# KGGRS2.net
KiCad netlist of a schematic drawn in EAGLE
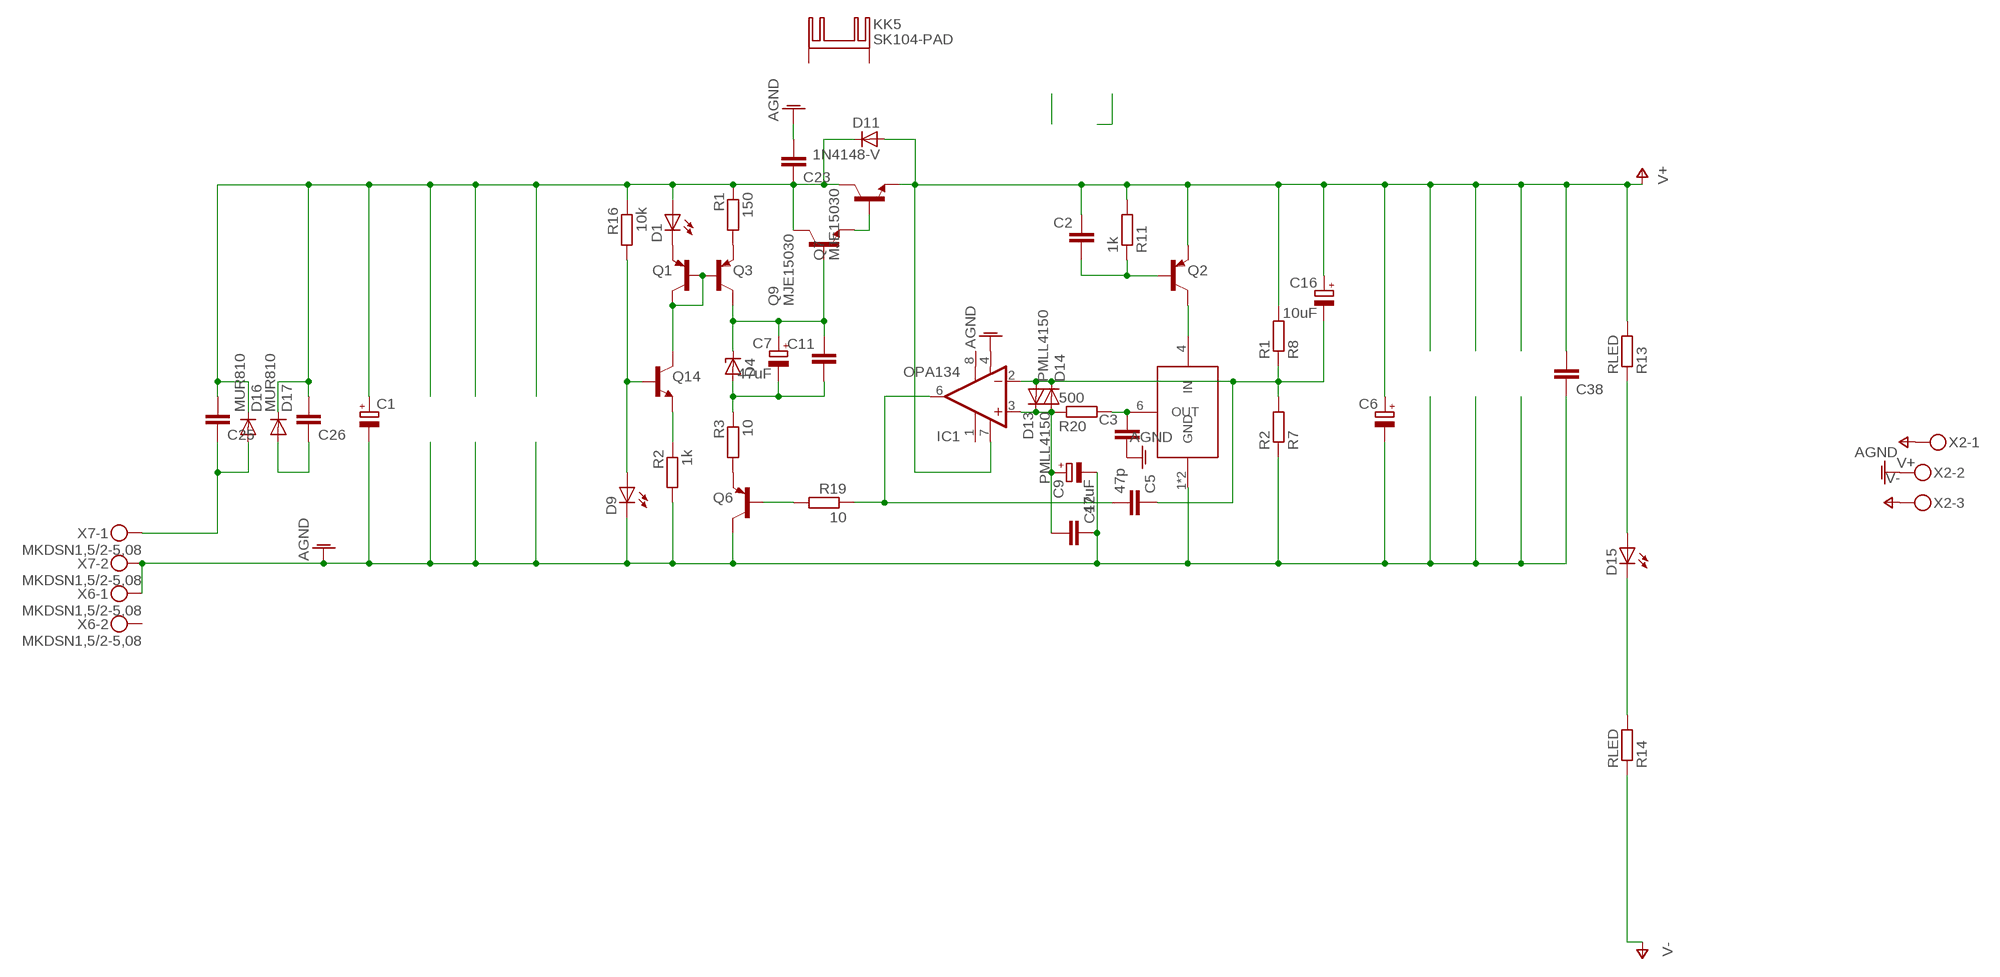
[diagram p0: schematic, sheet 1]

(export (version "E")
  (design (tool "Eeschema 10.0.6"))
  (components
    (comp (ref "C1")
      (value "CPOL-EUE10-35")
      (footprint "eagle-import:EB35D")
      (libsource (lib "eagle-import") (part "CPOL-EUE10-35"))
    )
    (comp (ref "C2")
      (value "C-EUC1206")
      (footprint "eagle-import:C1206")
      (libsource (lib "eagle-import") (part "C-EUC1206"))
    )
    (comp (ref "C3")
      (value "C-EUC1206")
      (footprint "eagle-import:C1206")
      (libsource (lib "eagle-import") (part "C-EUC1206"))
    )
    (comp (ref "C5")
      (value "47p")
      (footprint "eagle-import:C1206")
      (libsource (lib "eagle-import") (part "C-EUC1206"))
    )
    (comp (ref "C6")
      (value "CPOL-EUE5-13")
      (footprint "eagle-import:E5-13")
      (libsource (lib "eagle-import") (part "CPOL-EUE5-13"))
    )
    (comp (ref "C7")
      (value "47uF")
      (footprint "eagle-import:SP-CAP-CX")
      (libsource (lib "eagle-import") (part "CPOL-EUSP-CAP-CX"))
    )
    (comp (ref "C9")
      (value "47uF")
      (footprint "eagle-import:SP-CAP-CX")
      (libsource (lib "eagle-import") (part "CPOL-EUSP-CAP-CX"))
    )
    (comp (ref "C11")
      (value "C-EUC1206")
      (footprint "eagle-import:C1206")
      (libsource (lib "eagle-import") (part "C-EUC1206"))
    )
    (comp (ref "C12")
      (value "C-EU050-035X075")
      (footprint "eagle-import:C050-035X075")
      (libsource (lib "eagle-import") (part "C-EU050-035X075"))
    )
    (comp (ref "C16")
      (value "10uF")
      (footprint "eagle-import:SP-CAP-CX")
      (libsource (lib "eagle-import") (part "CPOL-EUSP-CAP-CX"))
    )
    (comp (ref "C23")
      (value "C-EU050-075X075")
      (footprint "eagle-import:C050-075X075")
      (libsource (lib "eagle-import") (part "C-EU050-075X075"))
    )
    (comp (ref "C25")
      (value "C-EU050-035X075")
      (footprint "eagle-import:C050-035X075")
      (libsource (lib "eagle-import") (part "C-EU050-035X075"))
    )
    (comp (ref "C26")
      (value "C-EU050-035X075")
      (footprint "eagle-import:C050-035X075")
      (libsource (lib "eagle-import") (part "C-EU050-035X075"))
    )
    (comp (ref "C38")
      (value "C-EU050-035X075")
      (footprint "eagle-import:C050-035X075")
      (libsource (lib "eagle-import") (part "C-EU050-035X075"))
    )
    (comp (ref "D1")
      (value "LED5MM")
      (footprint "eagle-import:LED5MM")
      (libsource (lib "eagle-import") (part "LED5MM"))
    )
    (comp (ref "D4")
      (value "ZENER-DIODESOD80C")
      (footprint "eagle-import:SOD80C")
      (libsource (lib "eagle-import") (part "ZENER-DIODESOD80C"))
    )
    (comp (ref "D9")
      (value "LED5MM")
      (footprint "eagle-import:LED5MM")
      (libsource (lib "eagle-import") (part "LED5MM"))
    )
    (comp (ref "D11")
      (value "1N4148-V")
      (footprint "eagle-import:1N4148")
      (libsource (lib "eagle-import") (part "1N4148-V"))
    )
    (comp (ref "D13")
      (value "PMLL4150")
      (footprint "eagle-import:SOD80C")
      (libsource (lib "eagle-import") (part "PMLL4150"))
    )
    (comp (ref "D14")
      (value "PMLL4150")
      (footprint "eagle-import:SOD80C")
      (libsource (lib "eagle-import") (part "PMLL4150"))
    )
    (comp (ref "D15")
      (value "LED5MM")
      (footprint "eagle-import:LED5MM")
      (libsource (lib "eagle-import") (part "LED5MM"))
    )
    (comp (ref "D16")
      (value "MUR810")
      (footprint "eagle-import:TO220ACS")
      (libsource (lib "eagle-import") (part "MUR810"))
    )
    (comp (ref "D17")
      (value "MUR810")
      (footprint "eagle-import:TO220ACS")
      (libsource (lib "eagle-import") (part "MUR810"))
    )
    (comp (ref "IC1")
      (value "OPA134")
      (footprint "eagle-import:SO08")
      (fields (field (name "MF") "TEXAS INSTRUMENTS") (field (name "MPN") "OPA134UA"))
      (libsource (lib "eagle-import") (part "OPA134U"))
    )
    (comp (ref "KK5")
      (value "SK104-PAD")
      (footprint "eagle-import:SK104-PAD")
      (libsource (lib "eagle-import") (part "SK104-PAD"))
    )
    (comp (ref "Q1")
      (value "MMBTA92LT1-PNP-SOT23-BEC")
      (footprint "eagle-import:SOT23-BEC")
      (libsource (lib "eagle-import") (part "-PNP-SOT23-BECMMBTA92LT1"))
    )
    (comp (ref "Q2")
      (value "MMBTA92LT1-PNP-SOT23-BEC")
      (footprint "eagle-import:SOT23-BEC")
      (libsource (lib "eagle-import") (part "-PNP-SOT23-BECMMBTA92LT1"))
    )
    (comp (ref "Q3")
      (value "MMBTA92LT1-PNP-SOT23-BEC")
      (footprint "eagle-import:SOT23-BEC")
      (libsource (lib "eagle-import") (part "-PNP-SOT23-BECMMBTA92LT1"))
    )
    (comp (ref "Q6")
      (value "MMBTA92LT1-PNP-SOT23-BEC")
      (footprint "eagle-import:SOT23-BEC")
      (libsource (lib "eagle-import") (part "-PNP-SOT23-BECMMBTA92LT1"))
    )
    (comp (ref "Q7")
      (value "MJE15030")
      (footprint "eagle-import:TO220KG")
      (libsource (lib "eagle-import") (part "MJE15030"))
    )
    (comp (ref "Q9")
      (value "MJE15030")
      (footprint "eagle-import:TO220KG")
      (libsource (lib "eagle-import") (part "MJE15030"))
    )
    (comp (ref "Q14")
      (value "MMBTA42LT1-NPN-SOT23-BEC")
      (footprint "eagle-import:SOT23-BEC")
      (libsource (lib "eagle-import") (part "-NPN-SOT23-BECMMBTA42LT1"))
    )
    (comp (ref "R1")
      (value "150")
      (footprint "eagle-import:MINI_MELF-0204W")
      (libsource (lib "eagle-import") (part "R-EU_MELF0204W"))
    )
    (comp (ref "R2")
      (value "1k")
      (footprint "eagle-import:MINI_MELF-0204W")
      (libsource (lib "eagle-import") (part "R-EU_MELF0204W"))
    )
    (comp (ref "R3")
      (value "10")
      (footprint "eagle-import:MINI_MELF-0204W")
      (libsource (lib "eagle-import") (part "R-EU_MELF0204W"))
    )
    (comp (ref "R7")
      (value "R2")
      (footprint "eagle-import:MINI_MELF-0204W")
      (libsource (lib "eagle-import") (part "R-EU_MELF0204W"))
    )
    (comp (ref "R8")
      (value "R1")
      (footprint "eagle-import:MINI_MELF-0204W")
      (libsource (lib "eagle-import") (part "R-EU_MELF0204W"))
    )
    (comp (ref "R11")
      (value "1k")
      (footprint "eagle-import:MINI_MELF-0204W")
      (libsource (lib "eagle-import") (part "R-EU_MELF0204W"))
    )
    (comp (ref "R13")
      (value "RLED")
      (footprint "eagle-import:MINI_MELF-0204W")
      (libsource (lib "eagle-import") (part "R-EU_MELF0204W"))
    )
    (comp (ref "R14")
      (value "RLED")
      (footprint "eagle-import:0207_2V")
      (libsource (lib "eagle-import") (part "R-EU_0207/2V"))
    )
    (comp (ref "R16")
      (value "10k")
      (footprint "eagle-import:MINI_MELF-0204W")
      (libsource (lib "eagle-import") (part "R-EU_MELF0204W"))
    )
    (comp (ref "R19")
      (value "10")
      (footprint "eagle-import:MINI_MELF-0204W")
      (libsource (lib "eagle-import") (part "R-EU_MELF0204W"))
    )
    (comp (ref "R20")
      (value "500")
      (footprint "eagle-import:MINI_MELF-0204W")
      (libsource (lib "eagle-import") (part "R-EU_MELF0204W"))
    )
    (comp (ref "U$1")
      (value "LTC6654")
      (footprint "eagle-import:SOT-23-6")
      (libsource (lib "eagle-import") (part "LTC6654"))
    )
    (comp (ref "X2")
      (value "MKDSN1,5/3-5,08")
      (footprint "eagle-import:MKDSN1,5_3-5,08")
      (libsource (lib "eagle-import") (part "MKDSN1,5/3-5,08"))
    )
    (comp (ref "X6")
      (value "MKDSN1,5/2-5,08")
      (footprint "eagle-import:MKDSN1,5_2-5,08")
      (libsource (lib "eagle-import") (part "MKDSN1,5/2-5,08"))
    )
    (comp (ref "X7")
      (value "MKDSN1,5/2-5,08")
      (footprint "eagle-import:MKDSN1,5_2-5,08")
      (libsource (lib "eagle-import") (part "MKDSN1,5/2-5,08"))
    )
  )
  (nets
    (net (code "1") (name "AGND") (class "Default")
      (node (ref "C1") (pin "-") (pinfunction "-_-") (pintype "passive"))
      (node (ref "C12") (pin "1") (pinfunction "1_1") (pintype "passive"))
      (node (ref "C23") (pin "2") (pinfunction "2_2") (pintype "passive"))
      (node (ref "C3") (pin "2") (pinfunction "2_2") (pintype "passive"))
      (node (ref "C38") (pin "1") (pinfunction "1_1") (pintype "passive"))
      (node (ref "C6") (pin "-") (pinfunction "-_-") (pintype "passive"))
      (node (ref "C9") (pin "-") (pinfunction "-_-") (pintype "passive"))
      (node (ref "D9") (pin "K") (pinfunction "C_K") (pintype "passive"))
      (node (ref "IC1") (pin "4") (pinfunction "V-_4") (pintype "power_in"))
      (node (ref "Q6") (pin "C") (pinfunction "C_C") (pintype "passive"))
      (node (ref "R2") (pin "2") (pinfunction "2_2") (pintype "passive"))
      (node (ref "R7") (pin "1") (pinfunction "1_1") (pintype "passive"))
      (node (ref "U$1") (pin "1") (pinfunction "GND_1") (pintype "bidirectional"))
      (node (ref "U$1") (pin "2") (pinfunction "GND_2") (pintype "bidirectional"))
      (node (ref "X2") (pin "2") (pinfunction "KL_2") (pintype "passive"))
      (node (ref "X6") (pin "1") (pinfunction "KL_1") (pintype "passive"))
      (node (ref "X7") (pin "2") (pinfunction "KL_2") (pintype "passive"))
    )
    (net (code "2") (name "Net-(C2-Pad2)") (class "Default")
      (node (ref "C2") (pin "2") (pinfunction "2_2") (pintype "passive"))
      (node (ref "Q2") (pin "B") (pinfunction "B_B") (pintype "passive"))
      (node (ref "R11") (pin "1") (pinfunction "1_1") (pintype "passive"))
    )
    (net (code "3") (name "Net-(C11-Pad2)") (class "Default")
      (node (ref "C11") (pin "2") (pinfunction "2_2") (pintype "passive"))
      (node (ref "C7") (pin "-") (pinfunction "-_-") (pintype "passive"))
      (node (ref "D4") (pin "A") (pinfunction "A_A") (pintype "passive"))
      (node (ref "R3") (pin "1") (pinfunction "1_1") (pintype "passive"))
    )
    (net (code "4") (name "Net-(C26-Pad1)") (class "Default")
      (node (ref "C26") (pin "1") (pinfunction "1_1") (pintype "passive"))
      (node (ref "D17") (pin "A") (pinfunction "A_A") (pintype "passive"))
    )
    (net (code "5") (name "Net-(D1-C)") (class "Default")
      (node (ref "D1") (pin "K") (pinfunction "C_K") (pintype "passive"))
      (node (ref "Q1") (pin "E") (pinfunction "E_E") (pintype "passive"))
    )
    (net (code "6") (name "Net-(D9-PadA)") (class "Default")
      (node (ref "D9") (pin "A") (pinfunction "A_A") (pintype "passive"))
      (node (ref "Q14") (pin "B") (pinfunction "B_B") (pintype "passive"))
      (node (ref "R16") (pin "2") (pinfunction "2_2") (pintype "passive"))
    )
    (net (code "7") (name "Net-(D15-C)") (class "Default")
      (node (ref "D15") (pin "K") (pinfunction "C_K") (pintype "passive"))
      (node (ref "R14") (pin "2") (pinfunction "2_2") (pintype "passive"))
    )
    (net (code "8") (name "Net-(D15-PadA)") (class "Default")
      (node (ref "D15") (pin "A") (pinfunction "A_A") (pintype "passive"))
      (node (ref "R13") (pin "1") (pinfunction "1_1") (pintype "passive"))
    )
    (net (code "9") (name "Net-(IC1-+IN)") (class "Default")
      (node (ref "C12") (pin "2") (pinfunction "2_2") (pintype "passive"))
      (node (ref "C9") (pin "+") (pinfunction "+_+") (pintype "passive"))
      (node (ref "D13") (pin "C") (pinfunction "C_C") (pintype "passive"))
      (node (ref "D14") (pin "A") (pinfunction "A_A") (pintype "passive"))
      (node (ref "IC1") (pin "3") (pinfunction "+IN_3") (pintype "input"))
      (node (ref "R20") (pin "1") (pinfunction "1_1") (pintype "passive"))
    )
    (net (code "10") (name "Net-(IC1--IN)") (class "Default")
      (node (ref "C16") (pin "-") (pinfunction "-_-") (pintype "passive"))
      (node (ref "C5") (pin "1") (pinfunction "1_1") (pintype "passive"))
      (node (ref "D13") (pin "A") (pinfunction "A_A") (pintype "passive"))
      (node (ref "D14") (pin "C") (pinfunction "C_C") (pintype "passive"))
      (node (ref "IC1") (pin "2") (pinfunction "-IN_2") (pintype "input"))
      (node (ref "R7") (pin "2") (pinfunction "2_2") (pintype "passive"))
      (node (ref "R8") (pin "1") (pinfunction "1_1") (pintype "passive"))
    )
    (net (code "11") (name "Net-(IC1-OUT)") (class "Default")
      (node (ref "C5") (pin "2") (pinfunction "2_2") (pintype "passive"))
      (node (ref "IC1") (pin "6") (pinfunction "OUT_6") (pintype "output"))
      (node (ref "R19") (pin "1") (pinfunction "1_1") (pintype "passive"))
    )
    (net (code "12") (name "Net-(Q1-PadB)") (class "Default")
      (node (ref "Q1") (pin "B") (pinfunction "B_B") (pintype "passive"))
      (node (ref "Q1") (pin "C") (pinfunction "C_C") (pintype "passive"))
      (node (ref "Q14") (pin "C") (pinfunction "C_C") (pintype "passive"))
      (node (ref "Q3") (pin "B") (pinfunction "B_B") (pintype "passive"))
    )
    (net (code "13") (name "Net-(Q3-PadE)") (class "Default")
      (node (ref "Q3") (pin "E") (pinfunction "E_E") (pintype "passive"))
      (node (ref "R1") (pin "2") (pinfunction "2_2") (pintype "passive"))
    )
    (net (code "14") (name "Net-(Q6-PadB)") (class "Default")
      (node (ref "Q6") (pin "B") (pinfunction "B_B") (pintype "passive"))
      (node (ref "R19") (pin "2") (pinfunction "2_2") (pintype "passive"))
    )
    (net (code "15") (name "Net-(Q6-PadE)") (class "Default")
      (node (ref "Q6") (pin "E") (pinfunction "E_E") (pintype "passive"))
      (node (ref "R3") (pin "2") (pinfunction "2_2") (pintype "passive"))
    )
    (net (code "16") (name "Net-(Q7-B)") (class "Default")
      (node (ref "Q7") (pin "1") (pinfunction "B_1") (pintype "passive"))
      (node (ref "Q9") (pin "3") (pinfunction "E_3") (pintype "passive"))
    )
    (net (code "17") (name "Net-(Q7-C)") (class "Default")
      (node (ref "C1") (pin "+") (pinfunction "+_+") (pintype "passive"))
      (node (ref "C23") (pin "1") (pinfunction "1_1") (pintype "passive"))
      (node (ref "C25") (pin "2") (pinfunction "2_2") (pintype "passive"))
      (node (ref "C26") (pin "2") (pinfunction "2_2") (pintype "passive"))
      (node (ref "D1") (pin "A") (pinfunction "A_A") (pintype "passive"))
      (node (ref "D11") (pin "C") (pinfunction "C_C") (pintype "passive"))
      (node (ref "D16") (pin "C") (pinfunction "C_C") (pintype "passive"))
      (node (ref "D17") (pin "C") (pinfunction "C_C") (pintype "passive"))
      (node (ref "Q7") (pin "2") (pinfunction "C_2") (pintype "passive"))
      (node (ref "Q9") (pin "2") (pinfunction "C_2") (pintype "passive"))
      (node (ref "R1") (pin "1") (pinfunction "1_1") (pintype "passive"))
      (node (ref "R16") (pin "1") (pinfunction "1_1") (pintype "passive"))
    )
    (net (code "18") (name "Net-(Q9-B)") (class "Default")
      (node (ref "C11") (pin "1") (pinfunction "1_1") (pintype "passive"))
      (node (ref "C7") (pin "+") (pinfunction "+_+") (pintype "passive"))
      (node (ref "D4") (pin "C") (pinfunction "C_C") (pintype "passive"))
      (node (ref "Q3") (pin "C") (pinfunction "C_C") (pintype "passive"))
      (node (ref "Q9") (pin "1") (pinfunction "B_1") (pintype "passive"))
    )
    (net (code "19") (name "Net-(Q14-PadE)") (class "Default")
      (node (ref "Q14") (pin "E") (pinfunction "E_E") (pintype "passive"))
      (node (ref "R2") (pin "1") (pinfunction "1_1") (pintype "passive"))
    )
    (net (code "20") (name "Net-(U$1-IN)") (class "Default")
      (node (ref "Q2") (pin "C") (pinfunction "C_C") (pintype "passive"))
      (node (ref "U$1") (pin "4") (pinfunction "IN_4") (pintype "bidirectional"))
    )
    (net (code "21") (name "Net-(U$1-OUT)") (class "Default")
      (node (ref "C3") (pin "1") (pinfunction "1_1") (pintype "passive"))
      (node (ref "R20") (pin "2") (pinfunction "2_2") (pintype "passive"))
      (node (ref "U$1") (pin "6") (pinfunction "OUT_6") (pintype "bidirectional"))
    )
    (net (code "22") (name "Net-(X7A-KL)") (class "Default")
      (node (ref "C25") (pin "1") (pinfunction "1_1") (pintype "passive"))
      (node (ref "D16") (pin "A") (pinfunction "A_A") (pintype "passive"))
      (node (ref "X7") (pin "1") (pinfunction "KL_1") (pintype "passive"))
    )
    (net (code "23") (name "V+") (class "Default")
      (node (ref "C16") (pin "+") (pinfunction "+_+") (pintype "passive"))
      (node (ref "C2") (pin "1") (pinfunction "1_1") (pintype "passive"))
      (node (ref "C38") (pin "2") (pinfunction "2_2") (pintype "passive"))
      (node (ref "C6") (pin "+") (pinfunction "+_+") (pintype "passive"))
      (node (ref "D11") (pin "A") (pinfunction "A_A") (pintype "passive"))
      (node (ref "IC1") (pin "7") (pinfunction "V+_7") (pintype "power_in"))
      (node (ref "Q2") (pin "E") (pinfunction "E_E") (pintype "passive"))
      (node (ref "Q7") (pin "3") (pinfunction "E_3") (pintype "passive"))
      (node (ref "R11") (pin "2") (pinfunction "2_2") (pintype "passive"))
      (node (ref "R13") (pin "2") (pinfunction "2_2") (pintype "passive"))
      (node (ref "R8") (pin "2") (pinfunction "2_2") (pintype "passive"))
      (node (ref "X2") (pin "1") (pinfunction "KL_1") (pintype "passive"))
    )
    (net (code "24") (name "V-") (class "Default")
      (node (ref "R14") (pin "1") (pinfunction "1_1") (pintype "passive"))
      (node (ref "X2") (pin "3") (pinfunction "KL_3") (pintype "passive"))
    )
    (net (code "25") (name "unconnected-(IC1-TRIM1-Pad1)") (class "Default")
      (node (ref "IC1") (pin "1") (pinfunction "TRIM1_1") (pintype "passive"))
    )
    (net (code "26") (name "unconnected-(IC1-TRIM2-Pad8)") (class "Default")
      (node (ref "IC1") (pin "8") (pinfunction "TRIM2_8") (pintype "passive"))
    )
    (net (code "27") (name "unconnected-(KK5-K-PadK1)") (class "Default")
      (node (ref "KK5") (pin "K1") (pinfunction "K_K1") (pintype "passive"))
    )
    (net (code "28") (name "unconnected-(KK5-K-PadK2)") (class "Default")
      (node (ref "KK5") (pin "K2") (pinfunction "K_K2") (pintype "passive"))
    )
    (net (code "29") (name "unconnected-(X6B-KL-Pad2)") (class "Default")
      (node (ref "X6") (pin "2") (pinfunction "KL_2") (pintype "passive"))
    )
  )
)
